# antenna_analyzer_rev7.net
KiCad netlist of a schematic drawn in EAGLE
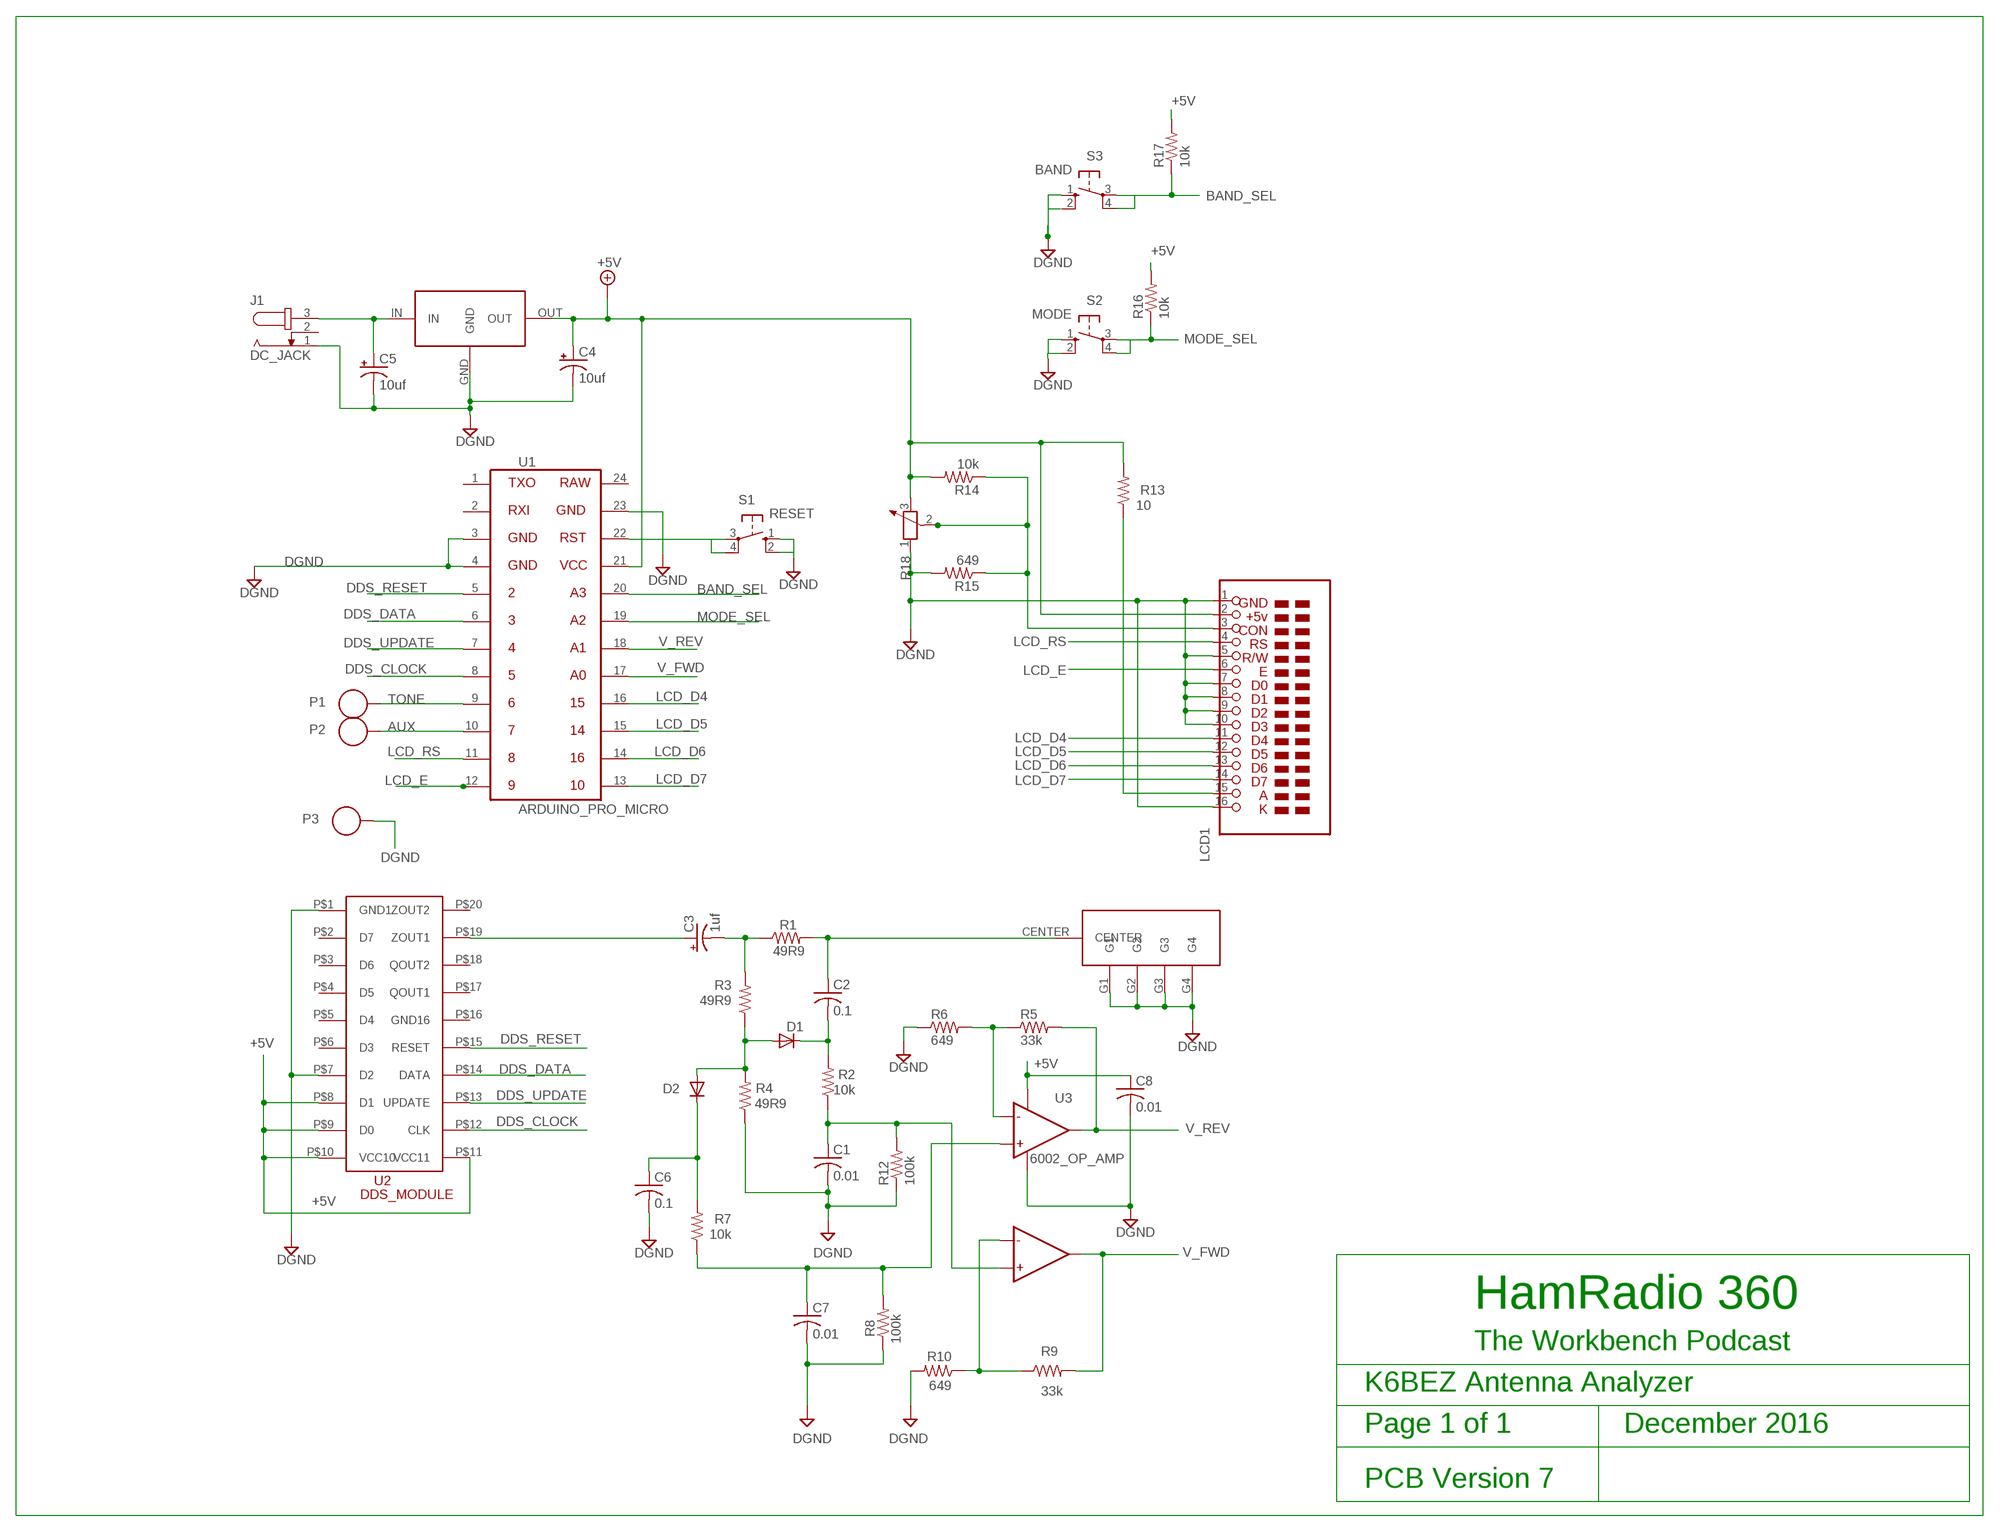
[diagram p0: schematic, sheet 1]

(export (version "E")
  (design (tool "Eeschema 10.0.6"))
  (components
    (comp (ref "C1")
      (value "0.01")
      (footprint "eagle-import:C025-025X050")
      (libsource (lib "eagle-import") (part "C-US025-025X050"))
    )
    (comp (ref "C2")
      (value "0.1")
      (footprint "eagle-import:C025-025X050")
      (libsource (lib "eagle-import") (part "C-US025-025X050"))
    )
    (comp (ref "C3")
      (value "1uf")
      (footprint "eagle-import:E1,8-4")
      (libsource (lib "eagle-import") (part "CPOL-USE1.8-4"))
    )
    (comp (ref "C4")
      (value "10uf")
      (footprint "eagle-import:E1,8-4")
      (libsource (lib "eagle-import") (part "CPOL-USE1.8-4"))
    )
    (comp (ref "C5")
      (value "10uf")
      (footprint "eagle-import:E1,8-4")
      (libsource (lib "eagle-import") (part "CPOL-USE1.8-4"))
    )
    (comp (ref "C6")
      (value "0.1")
      (footprint "eagle-import:C025-025X050")
      (libsource (lib "eagle-import") (part "C-US025-025X050"))
    )
    (comp (ref "C7")
      (value "0.01")
      (footprint "eagle-import:C025-025X050")
      (libsource (lib "eagle-import") (part "C-US025-025X050"))
    )
    (comp (ref "C8")
      (value "0.01")
      (footprint "eagle-import:C025-025X050")
      (libsource (lib "eagle-import") (part "C-US025-025X050"))
    )
    (comp (ref "CON1")
      (value "BNC-SMALL")
      (footprint "eagle-import:BNC-SMALL")
      (libsource (lib "eagle-import") (part "BNC-SMALL"))
    )
    (comp (ref "D1")
      (value "AA143")
      (footprint "eagle-import:DO35-7")
      (libsource (lib "eagle-import") (part "1N4148DO35-7"))
    )
    (comp (ref "D2")
      (value "AA143")
      (footprint "eagle-import:DO35-7")
      (libsource (lib "eagle-import") (part "1N4148DO35-7"))
    )
    (comp (ref "J1")
      (value "DC_JACK")
      (footprint "eagle-import:DC_COAXIAL_JACK")
      (libsource (lib "eagle-import") (part "DC_JACK"))
    )
    (comp (ref "LCD1")
      (value "LCD_2_16")
      (footprint "eagle-import:LCD_2X16")
      (libsource (lib "eagle-import") (part "LCD_2_16"))
    )
    (comp (ref "P1")
      (value "SOLDER_PAD_35_HOLE")
      (footprint "eagle-import:SOLDER_PAD_35_HOLE")
      (libsource (lib "eagle-import") (part "SOLDER_PAD_35_HOLE"))
    )
    (comp (ref "P2")
      (value "SOLDER_PAD_35_HOLE")
      (footprint "eagle-import:SOLDER_PAD_35_HOLE")
      (libsource (lib "eagle-import") (part "SOLDER_PAD_35_HOLE"))
    )
    (comp (ref "P3")
      (value "SOLDER_PAD_35_HOLE")
      (footprint "eagle-import:SOLDER_PAD_35_HOLE")
      (libsource (lib "eagle-import") (part "SOLDER_PAD_35_HOLE"))
    )
    (comp (ref "R1")
      (value "49R9")
      (footprint "eagle-import:0207_10")
      (libsource (lib "eagle-import") (part "R-US_0207/10"))
    )
    (comp (ref "R2")
      (value "10k")
      (footprint "eagle-import:0207_10")
      (libsource (lib "eagle-import") (part "R-US_0207/10"))
    )
    (comp (ref "R3")
      (value "49R9")
      (footprint "eagle-import:0207_10")
      (libsource (lib "eagle-import") (part "R-US_0207/10"))
    )
    (comp (ref "R4")
      (value "49R9")
      (footprint "eagle-import:0207_10")
      (libsource (lib "eagle-import") (part "R-US_0207/10"))
    )
    (comp (ref "R5")
      (value "33k")
      (footprint "eagle-import:0207_10")
      (libsource (lib "eagle-import") (part "R-US_0207/10"))
    )
    (comp (ref "R6")
      (value "649")
      (footprint "eagle-import:0207_10")
      (libsource (lib "eagle-import") (part "R-US_0207/10"))
    )
    (comp (ref "R7")
      (value "10k")
      (footprint "eagle-import:0207_10")
      (libsource (lib "eagle-import") (part "R-US_0207/10"))
    )
    (comp (ref "R8")
      (value "100k")
      (footprint "eagle-import:0207_10")
      (libsource (lib "eagle-import") (part "R-US_0207/10"))
    )
    (comp (ref "R9")
      (value "33k")
      (footprint "eagle-import:0207_10")
      (libsource (lib "eagle-import") (part "R-US_0207/10"))
    )
    (comp (ref "R10")
      (value "649")
      (footprint "eagle-import:0207_10")
      (libsource (lib "eagle-import") (part "R-US_0207/10"))
    )
    (comp (ref "R12")
      (value "100k")
      (footprint "eagle-import:0207_10")
      (libsource (lib "eagle-import") (part "R-US_0207/10"))
    )
    (comp (ref "R13")
      (value "10")
      (footprint "eagle-import:0207_10")
      (libsource (lib "eagle-import") (part "R-US_0207/10"))
    )
    (comp (ref "R14")
      (value "10k")
      (footprint "eagle-import:0207_10")
      (libsource (lib "eagle-import") (part "R-US_0207/10"))
    )
    (comp (ref "R15")
      (value "649")
      (footprint "eagle-import:0207_10")
      (libsource (lib "eagle-import") (part "R-US_0207/10"))
    )
    (comp (ref "R16")
      (value "10k")
      (footprint "eagle-import:0207_10")
      (libsource (lib "eagle-import") (part "R-US_0207/10"))
    )
    (comp (ref "R17")
      (value "10k")
      (footprint "eagle-import:0207_10")
      (libsource (lib "eagle-import") (part "R-US_0207/10"))
    )
    (comp (ref "R18")
      (value "R-POTENTIOMETER-3362U")
      (footprint "eagle-import:3362U")
      (libsource (lib "eagle-import") (part "R-POTENTIOMETER-3362U"))
    )
    (comp (ref "S1")
      (value "RESET")
      (footprint "eagle-import:B3F-10XX")
      (fields (field (name "MPN") "B3F-1000"))
      (libsource (lib "eagle-import") (part "10-XX"))
    )
    (comp (ref "S2")
      (value "MODE")
      (footprint "eagle-import:B3F-10XX")
      (fields (field (name "MPN") "B3F-1000"))
      (libsource (lib "eagle-import") (part "10-XX"))
    )
    (comp (ref "S3")
      (value "BAND")
      (footprint "eagle-import:B3F-10XX")
      (fields (field (name "MPN") "B3F-1000"))
      (libsource (lib "eagle-import") (part "10-XX"))
    )
    (comp (ref "U1")
      (value "ARDUINO_PRO_MICRO")
      (footprint "eagle-import:ARDUINO_PRO_MICRO")
      (libsource (lib "eagle-import") (part "ARDUINO_PRO_MICRO"))
    )
    (comp (ref "U2")
      (value "AD9850_MOD")
      (footprint "eagle-import:DDS_DIL")
      (libsource (lib "eagle-import") (part "AD9850_MOD"))
    )
    (comp (ref "U3")
      (value "6002_OP_AMP")
      (footprint "eagle-import:OP_AMP_8_PIN")
      (libsource (lib "eagle-import") (part "6002_OP_AMP"))
    )
    (comp (ref "U5")
      (value "SWITCHING_REGULATOR")
      (footprint "eagle-import:SWITCHING_REGULATOR")
      (libsource (lib "eagle-import") (part "SWITCHING_REGULATOR"))
    )
  )
  (nets
    (net (code "1") (name "+5V") (class "Default")
      (node (ref "C4") (pin "+") (pinfunction "+_+") (pintype "passive"))
      (node (ref "C8") (pin "1") (pinfunction "1_1") (pintype "passive"))
      (node (ref "LCD1") (pin "2") (pinfunction "2_2") (pintype "passive"))
      (node (ref "R13") (pin "2") (pinfunction "2_2") (pintype "passive"))
      (node (ref "R14") (pin "2") (pinfunction "2_2") (pintype "passive"))
      (node (ref "R16") (pin "2") (pinfunction "2_2") (pintype "passive"))
      (node (ref "R17") (pin "2") (pinfunction "2_2") (pintype "passive"))
      (node (ref "R18") (pin "3") (pinfunction "2_3") (pintype "passive"))
      (node (ref "U1") (pin "21") (pinfunction "21_21") (pintype "input"))
      (node (ref "U2") (pin "P$10") (pinfunction "VCC10_P$10") (pintype "bidirectional"))
      (node (ref "U2") (pin "P$11") (pinfunction "VCC11_P$11") (pintype "bidirectional"))
      (node (ref "U2") (pin "P$8") (pinfunction "D1_P$8") (pintype "bidirectional"))
      (node (ref "U2") (pin "P$9") (pinfunction "D0_P$9") (pintype "bidirectional"))
      (node (ref "U3") (pin "8") (pinfunction "VCC+_8") (pintype "power_in"))
      (node (ref "U5") (pin "OUT") (pinfunction "OUT_OUT") (pintype "bidirectional"))
    )
    (net (code "2") (name "/AUX") (class "Default")
      (node (ref "P2") (pin "1") (pinfunction "1_1") (pintype "bidirectional"))
      (node (ref "U1") (pin "10") (pinfunction "10_10") (pintype "input"))
    )
    (net (code "3") (name "/BAND_SEL") (class "Default")
      (node (ref "R17") (pin "1") (pinfunction "1_1") (pintype "passive"))
      (node (ref "S3") (pin "3") (pinfunction "P_3") (pintype "passive"))
      (node (ref "S3") (pin "4") (pinfunction "P1_4") (pintype "passive"))
      (node (ref "U1") (pin "20") (pinfunction "20_20") (pintype "input"))
    )
    (net (code "4") (name "/DDS_CLOCK") (class "Default")
      (node (ref "U1") (pin "8") (pinfunction "8_8") (pintype "input"))
      (node (ref "U2") (pin "P$12") (pinfunction "CLK_P$12") (pintype "bidirectional"))
    )
    (net (code "5") (name "/DDS_DATA") (class "Default")
      (node (ref "U1") (pin "6") (pinfunction "6_6") (pintype "input"))
      (node (ref "U2") (pin "P$14") (pinfunction "DATA_P$14") (pintype "bidirectional"))
    )
    (net (code "6") (name "/DDS_RESET") (class "Default")
      (node (ref "U1") (pin "5") (pinfunction "5_5") (pintype "input"))
      (node (ref "U2") (pin "P$15") (pinfunction "RESET_P$15") (pintype "bidirectional"))
    )
    (net (code "7") (name "/DDS_UPDATE") (class "Default")
      (node (ref "U1") (pin "7") (pinfunction "7_7") (pintype "input"))
      (node (ref "U2") (pin "P$13") (pinfunction "UPDATE_P$13") (pintype "bidirectional"))
    )
    (net (code "8") (name "/LCD_D4") (class "Default")
      (node (ref "LCD1") (pin "11") (pinfunction "11_11") (pintype "passive"))
      (node (ref "U1") (pin "16") (pinfunction "16_16") (pintype "input"))
    )
    (net (code "9") (name "/LCD_D5") (class "Default")
      (node (ref "LCD1") (pin "12") (pinfunction "12_12") (pintype "passive"))
      (node (ref "U1") (pin "15") (pinfunction "15_15") (pintype "tri_state"))
    )
    (net (code "10") (name "/LCD_D6") (class "Default")
      (node (ref "LCD1") (pin "13") (pinfunction "13_13") (pintype "passive"))
      (node (ref "U1") (pin "14") (pinfunction "14_14") (pintype "input"))
    )
    (net (code "11") (name "/LCD_D7") (class "Default")
      (node (ref "LCD1") (pin "14") (pinfunction "14_14") (pintype "passive"))
      (node (ref "U1") (pin "13") (pinfunction "13_13") (pintype "input"))
    )
    (net (code "12") (name "/LCD_E") (class "Default")
      (node (ref "LCD1") (pin "6") (pinfunction "6_6") (pintype "passive"))
      (node (ref "U1") (pin "12") (pinfunction "12_12") (pintype "input"))
    )
    (net (code "13") (name "/LCD_RS") (class "Default")
      (node (ref "LCD1") (pin "4") (pinfunction "4_4") (pintype "passive"))
      (node (ref "U1") (pin "11") (pinfunction "11_11") (pintype "input"))
    )
    (net (code "14") (name "/MODE_SEL") (class "Default")
      (node (ref "R16") (pin "1") (pinfunction "1_1") (pintype "passive"))
      (node (ref "S2") (pin "3") (pinfunction "P_3") (pintype "passive"))
      (node (ref "S2") (pin "4") (pinfunction "P1_4") (pintype "passive"))
      (node (ref "U1") (pin "19") (pinfunction "19_19") (pintype "input"))
    )
    (net (code "16") (name "/TONE") (class "Default")
      (node (ref "P1") (pin "1") (pinfunction "1_1") (pintype "bidirectional"))
      (node (ref "U1") (pin "9") (pinfunction "9_9") (pintype "input"))
    )
    (net (code "17") (name "/V_FWD") (class "Default")
      (node (ref "R9") (pin "2") (pinfunction "2_2") (pintype "passive"))
      (node (ref "U1") (pin "17") (pinfunction "17_17") (pintype "input"))
      (node (ref "U3") (pin "7") (pinfunction "OUT2_7") (pintype "output"))
    )
    (net (code "18") (name "/V_REV") (class "Default")
      (node (ref "R5") (pin "2") (pinfunction "2_2") (pintype "passive"))
      (node (ref "U1") (pin "18") (pinfunction "18_18") (pintype "input"))
      (node (ref "U3") (pin "1") (pinfunction "OUT1_1") (pintype "output"))
    )
    (net (code "19") (name "DGND") (class "Default")
      (node (ref "C1") (pin "2") (pinfunction "2_2") (pintype "passive"))
      (node (ref "C4") (pin "-") (pinfunction "-_-") (pintype "passive"))
      (node (ref "C5") (pin "-") (pinfunction "-_-") (pintype "passive"))
      (node (ref "C6") (pin "2") (pinfunction "2_2") (pintype "passive"))
      (node (ref "C7") (pin "2") (pinfunction "2_2") (pintype "passive"))
      (node (ref "C8") (pin "2") (pinfunction "2_2") (pintype "passive"))
      (node (ref "CON1") (pin "G1") (pinfunction "G1_G1") (pintype "bidirectional"))
      (node (ref "CON1") (pin "G2") (pinfunction "G2_G2") (pintype "bidirectional"))
      (node (ref "CON1") (pin "G3") (pinfunction "G3_G3") (pintype "bidirectional"))
      (node (ref "CON1") (pin "G4") (pinfunction "G4_G4") (pintype "bidirectional"))
      (node (ref "J1") (pin "1") (pinfunction "1_1") (pintype "passive"))
      (node (ref "LCD1") (pin "1") (pinfunction "1_1") (pintype "passive"))
      (node (ref "LCD1") (pin "10") (pinfunction "10_10") (pintype "passive"))
      (node (ref "LCD1") (pin "16") (pinfunction "16_16") (pintype "passive"))
      (node (ref "LCD1") (pin "5") (pinfunction "5_5") (pintype "passive"))
      (node (ref "LCD1") (pin "7") (pinfunction "7_7") (pintype "passive"))
      (node (ref "LCD1") (pin "8") (pinfunction "8_8") (pintype "passive"))
      (node (ref "LCD1") (pin "9") (pinfunction "9_9") (pintype "passive"))
      (node (ref "P3") (pin "1") (pinfunction "1_1") (pintype "bidirectional"))
      (node (ref "R10") (pin "2") (pinfunction "2_2") (pintype "passive"))
      (node (ref "R12") (pin "1") (pinfunction "1_1") (pintype "passive"))
      (node (ref "R15") (pin "2") (pinfunction "2_2") (pintype "passive"))
      (node (ref "R18") (pin "1") (pinfunction "1_1") (pintype "passive"))
      (node (ref "R4") (pin "1") (pinfunction "1_1") (pintype "passive"))
      (node (ref "R6") (pin "1") (pinfunction "1_1") (pintype "passive"))
      (node (ref "R8") (pin "1") (pinfunction "1_1") (pintype "passive"))
      (node (ref "S1") (pin "1") (pinfunction "S_1") (pintype "passive"))
      (node (ref "S1") (pin "2") (pinfunction "S1_2") (pintype "passive"))
      (node (ref "S2") (pin "1") (pinfunction "S_1") (pintype "passive"))
      (node (ref "S2") (pin "2") (pinfunction "S1_2") (pintype "passive"))
      (node (ref "S3") (pin "1") (pinfunction "S_1") (pintype "passive"))
      (node (ref "U1") (pin "23") (pinfunction "23_23") (pintype "input"))
      (node (ref "U1") (pin "3") (pinfunction "3_3") (pintype "input"))
      (node (ref "U1") (pin "4") (pinfunction "4_4") (pintype "input"))
      (node (ref "U2") (pin "P$1") (pinfunction "GND1_P$1") (pintype "bidirectional"))
      (node (ref "U2") (pin "P$7") (pinfunction "D2_P$7") (pintype "bidirectional"))
      (node (ref "U3") (pin "4") (pinfunction "VCC-_4") (pintype "power_in"))
      (node (ref "U5") (pin "GND") (pinfunction "GND_GND") (pintype "bidirectional"))
    )
    (net (code "20") (name "Net-(C2-Pad1)") (class "Default")
      (node (ref "C2") (pin "1") (pinfunction "1_1") (pintype "passive"))
      (node (ref "CON1") (pin "CENTER") (pinfunction "CENTER_CENTER") (pintype "bidirectional"))
      (node (ref "R1") (pin "2") (pinfunction "2_2") (pintype "passive"))
    )
    (net (code "21") (name "Net-(C2-Pad2)") (class "Default")
      (node (ref "C2") (pin "2") (pinfunction "2_2") (pintype "passive"))
      (node (ref "D1") (pin "C") (pinfunction "C_C") (pintype "passive"))
      (node (ref "R2") (pin "2") (pinfunction "2_2") (pintype "passive"))
    )
    (net (code "22") (name "Net-(C3-Pad-)") (class "Default")
      (node (ref "C3") (pin "-") (pinfunction "-_-") (pintype "passive"))
      (node (ref "R1") (pin "1") (pinfunction "1_1") (pintype "passive"))
      (node (ref "R3") (pin "2") (pinfunction "2_2") (pintype "passive"))
    )
    (net (code "23") (name "Net-(C5-Pad+)") (class "Default")
      (node (ref "C5") (pin "+") (pinfunction "+_+") (pintype "passive"))
      (node (ref "J1") (pin "3") (pinfunction "3_3") (pintype "passive"))
      (node (ref "U5") (pin "IN") (pinfunction "IN_IN") (pintype "bidirectional"))
    )
    (net (code "24") (name "Net-(C6-Pad1)") (class "Default")
      (node (ref "C6") (pin "1") (pinfunction "1_1") (pintype "passive"))
      (node (ref "D2") (pin "C") (pinfunction "C_C") (pintype "passive"))
      (node (ref "R7") (pin "2") (pinfunction "2_2") (pintype "passive"))
    )
    (net (code "25") (name "Net-(D1-PadA)") (class "Default")
      (node (ref "D1") (pin "A") (pinfunction "A_A") (pintype "passive"))
      (node (ref "D2") (pin "A") (pinfunction "A_A") (pintype "passive"))
      (node (ref "R3") (pin "1") (pinfunction "1_1") (pintype "passive"))
      (node (ref "R4") (pin "2") (pinfunction "2_2") (pintype "passive"))
    )
    (net (code "26") (name "Net-(LCD1-Pad15)") (class "Default")
      (node (ref "LCD1") (pin "15") (pinfunction "15_15") (pintype "passive"))
      (node (ref "R13") (pin "1") (pinfunction "1_1") (pintype "passive"))
    )
    (net (code "27") (name "Net-(R18-3)") (class "Default")
      (node (ref "LCD1") (pin "3") (pinfunction "3_3") (pintype "passive"))
      (node (ref "R14") (pin "1") (pinfunction "1_1") (pintype "passive"))
      (node (ref "R15") (pin "1") (pinfunction "1_1") (pintype "passive"))
      (node (ref "R18") (pin "2") (pinfunction "3_2") (pintype "passive"))
    )
    (net (code "28") (name "Net-(S1-P)") (class "Default")
      (node (ref "S1") (pin "3") (pinfunction "P_3") (pintype "passive"))
      (node (ref "S1") (pin "4") (pinfunction "P1_4") (pintype "passive"))
      (node (ref "U1") (pin "22") (pinfunction "22_22") (pintype "input"))
    )
    (net (code "29") (name "Net-(U2-ZOUT1)") (class "Default")
      (node (ref "C3") (pin "+") (pinfunction "+_+") (pintype "passive"))
      (node (ref "U2") (pin "P$19") (pinfunction "ZOUT1_P$19") (pintype "bidirectional"))
    )
    (net (code "30") (name "Net-(U3-IN+1)") (class "Default")
      (node (ref "C7") (pin "1") (pinfunction "1_1") (pintype "passive"))
      (node (ref "R7") (pin "1") (pinfunction "1_1") (pintype "passive"))
      (node (ref "R8") (pin "2") (pinfunction "2_2") (pintype "passive"))
      (node (ref "U3") (pin "3") (pinfunction "IN+1_3") (pintype "input"))
    )
    (net (code "31") (name "Net-(U3-IN+2)") (class "Default")
      (node (ref "C1") (pin "1") (pinfunction "1_1") (pintype "passive"))
      (node (ref "R12") (pin "2") (pinfunction "2_2") (pintype "passive"))
      (node (ref "R2") (pin "1") (pinfunction "1_1") (pintype "passive"))
      (node (ref "U3") (pin "5") (pinfunction "IN+2_5") (pintype "input"))
    )
    (net (code "32") (name "Net-(U3-IN-1)") (class "Default")
      (node (ref "R5") (pin "1") (pinfunction "1_1") (pintype "passive"))
      (node (ref "R6") (pin "2") (pinfunction "2_2") (pintype "passive"))
      (node (ref "U3") (pin "2") (pinfunction "IN-1_2") (pintype "input"))
    )
    (net (code "33") (name "Net-(U3-IN-2)") (class "Default")
      (node (ref "R10") (pin "1") (pinfunction "1_1") (pintype "passive"))
      (node (ref "R9") (pin "1") (pinfunction "1_1") (pintype "passive"))
      (node (ref "U3") (pin "6") (pinfunction "IN-2_6") (pintype "input"))
    )
    (net (code "34") (name "unconnected-(J1-Pad2)") (class "Default")
      (node (ref "J1") (pin "2") (pinfunction "2_2") (pintype "passive"))
    )
    (net (code "35") (name "unconnected-(S3-S1-Pad2)") (class "Default")
      (node (ref "S3") (pin "2") (pinfunction "S1_2") (pintype "passive"))
    )
    (net (code "36") (name "unconnected-(U1-Pad1)") (class "Default")
      (node (ref "U1") (pin "1") (pinfunction "1_1") (pintype "input"))
    )
    (net (code "37") (name "unconnected-(U1-Pad2)") (class "Default")
      (node (ref "U1") (pin "2") (pinfunction "2_2") (pintype "input"))
    )
    (net (code "38") (name "unconnected-(U1-Pad24)") (class "Default")
      (node (ref "U1") (pin "24") (pinfunction "24_24") (pintype "input"))
    )
    (net (code "39") (name "unconnected-(U2-D3-PadP$6)") (class "Default")
      (node (ref "U2") (pin "P$6") (pinfunction "D3_P$6") (pintype "bidirectional"))
    )
    (net (code "40") (name "unconnected-(U2-D4-PadP$5)") (class "Default")
      (node (ref "U2") (pin "P$5") (pinfunction "D4_P$5") (pintype "bidirectional"))
    )
    (net (code "41") (name "unconnected-(U2-D5-PadP$4)") (class "Default")
      (node (ref "U2") (pin "P$4") (pinfunction "D5_P$4") (pintype "bidirectional"))
    )
    (net (code "42") (name "unconnected-(U2-D6-PadP$3)") (class "Default")
      (node (ref "U2") (pin "P$3") (pinfunction "D6_P$3") (pintype "bidirectional"))
    )
    (net (code "43") (name "unconnected-(U2-D7-PadP$2)") (class "Default")
      (node (ref "U2") (pin "P$2") (pinfunction "D7_P$2") (pintype "bidirectional"))
    )
    (net (code "44") (name "unconnected-(U2-GND16-PadP$16)") (class "Default")
      (node (ref "U2") (pin "P$16") (pinfunction "GND16_P$16") (pintype "bidirectional"))
    )
    (net (code "45") (name "unconnected-(U2-QOUT1-PadP$17)") (class "Default")
      (node (ref "U2") (pin "P$17") (pinfunction "QOUT1_P$17") (pintype "bidirectional"))
    )
    (net (code "46") (name "unconnected-(U2-QOUT2-PadP$18)") (class "Default")
      (node (ref "U2") (pin "P$18") (pinfunction "QOUT2_P$18") (pintype "bidirectional"))
    )
    (net (code "47") (name "unconnected-(U2-ZOUT2-PadP$20)") (class "Default")
      (node (ref "U2") (pin "P$20") (pinfunction "ZOUT2_P$20") (pintype "bidirectional"))
    )
  )
)
